# MCU.net
KiCad netlist of a schematic drawn in Altium Designer
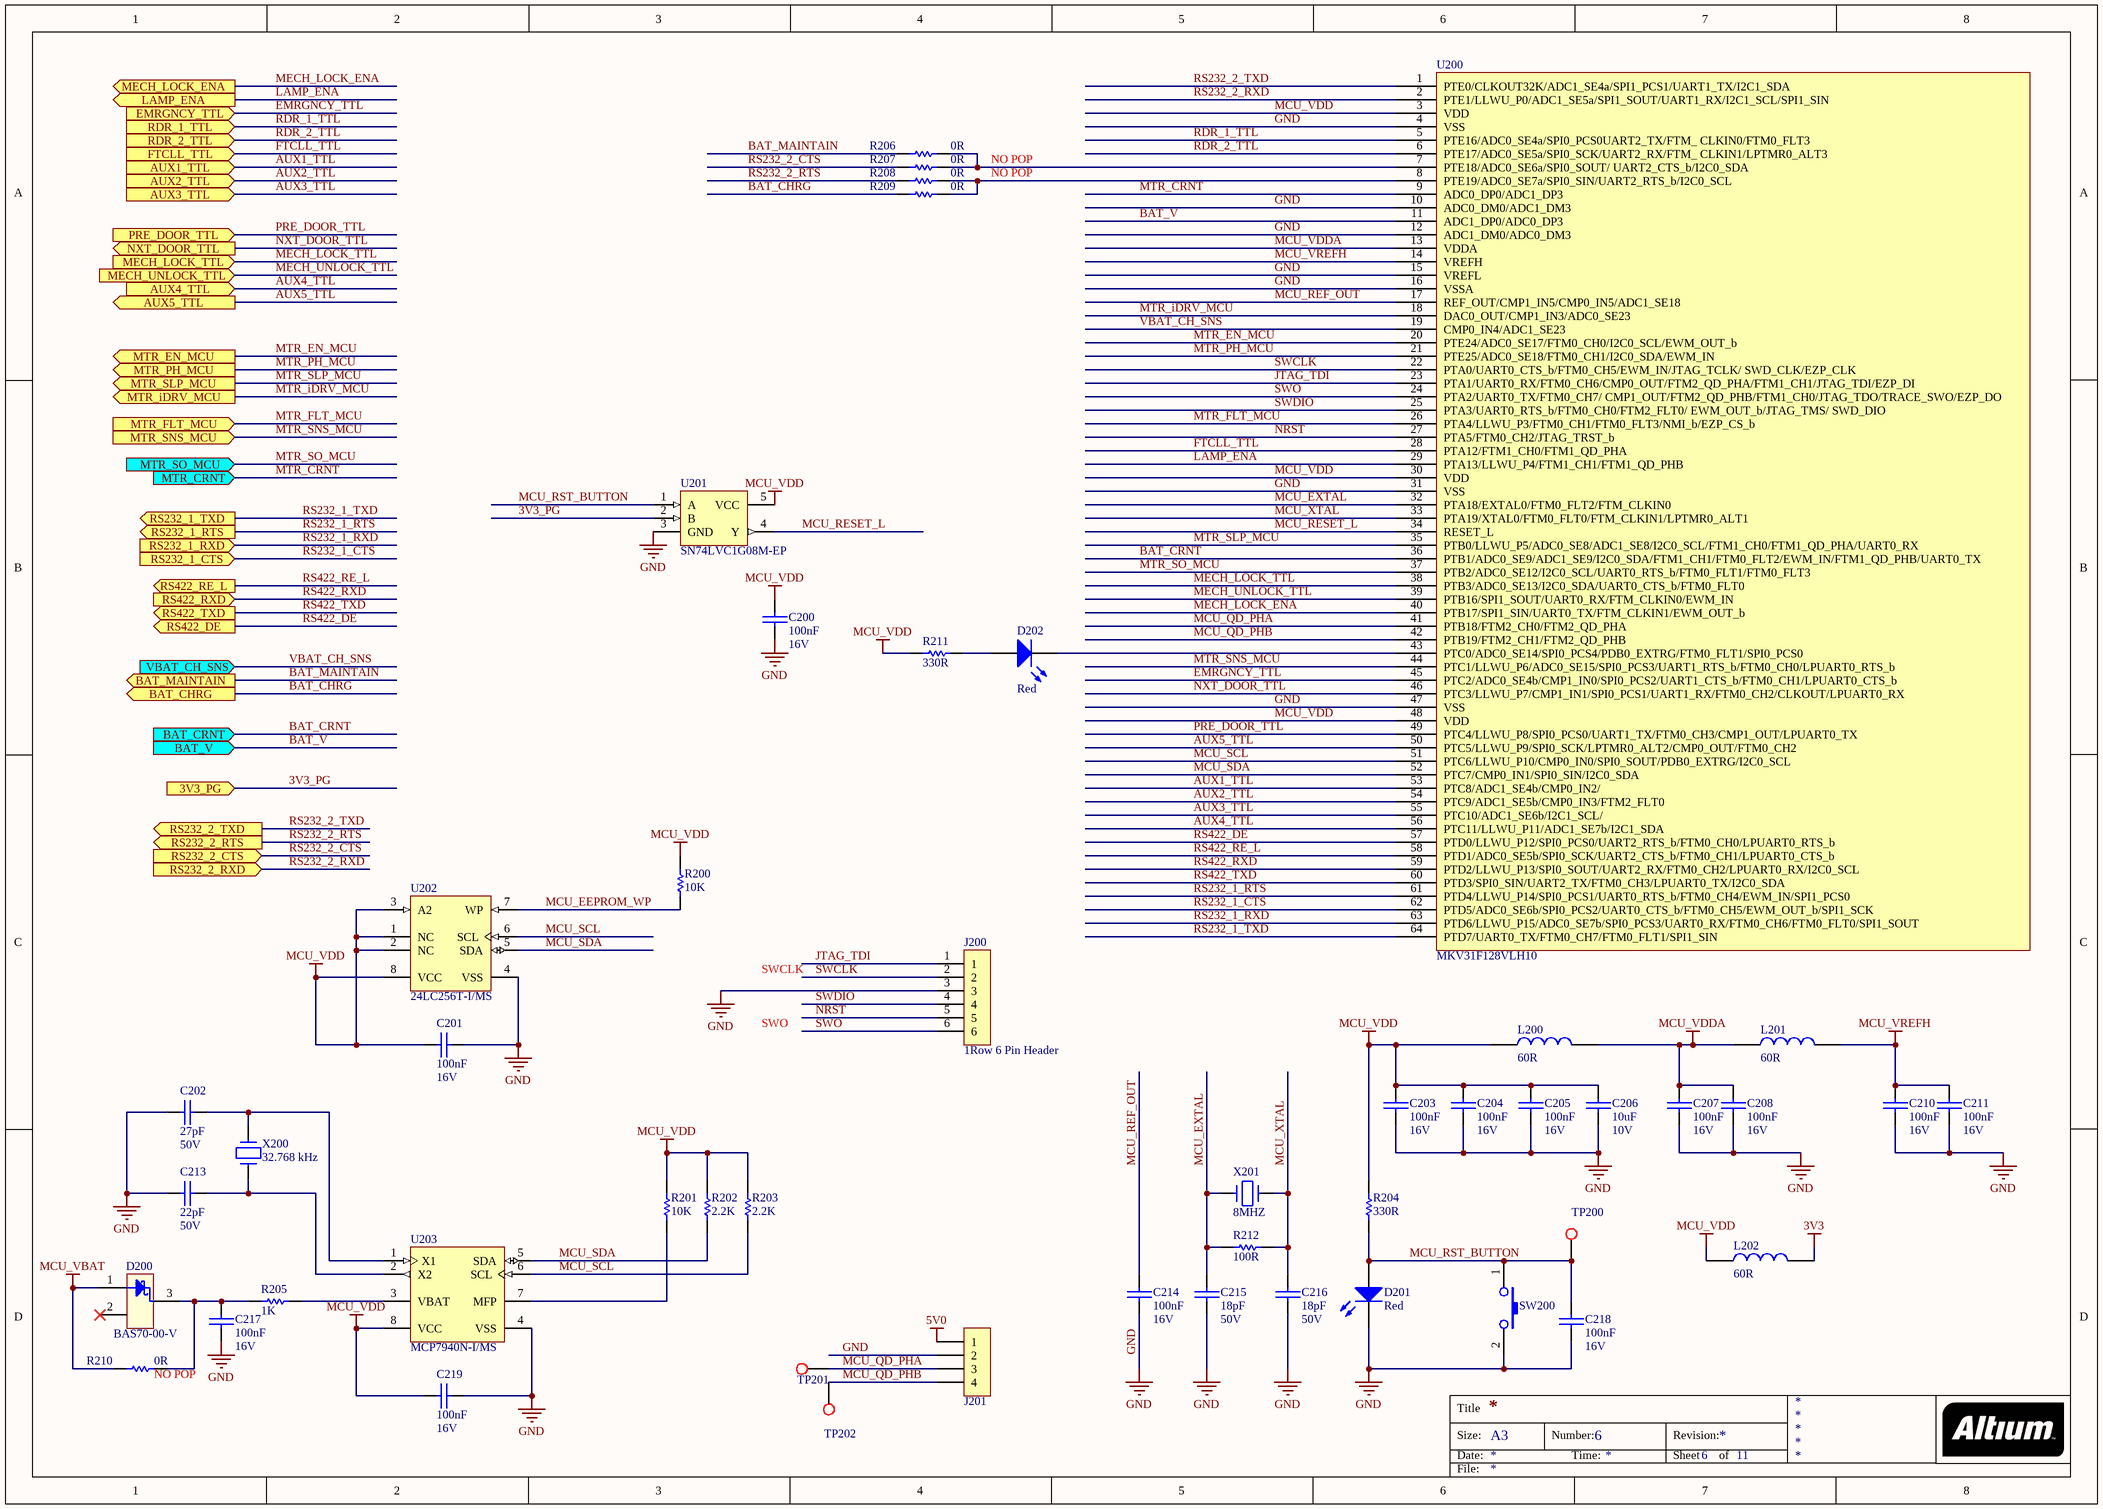
[diagram p0: MCU.SchDoc]

(export (version "E")
  (design (tool "Eeschema 10.0.6"))
  (components
    (comp (ref "C200")
      (value "100nF")
      (footprint "CAPC1005X06N")
      (description "CAP, CER, X7R, 100nF, %10, 16V, 0402")
      (fields
        (field (name "MANUFACTURER") "Murata")
        (field (name "MANUFACTURER PART NUMBER") "GRM155R71C104KA88D")
        (field (name "OPERATING VOLTAGE") "16V")
      )
      (libsource (lib "Anime_Capacitor") (part "ACC7-2100-S241-0000"))
    )
    (comp (ref "C201")
      (value "100nF")
      (footprint "CAPC1005X06N")
      (description "CAP, CER, X7R, 100nF, %10, 16V, 0402")
      (fields
        (field (name "MANUFACTURER") "Murata")
        (field (name "MANUFACTURER PART NUMBER") "GRM155R71C104KA88D")
        (field (name "OPERATING VOLTAGE") "16V")
      )
      (libsource (lib "Anime_Capacitor") (part "ACC7-2100-S241-0000"))
    )
    (comp (ref "C202")
      (value "27pF")
      (footprint "CAPC1005X06N")
      (description "CAP, CER, C0G, 27pF, %5, 50V, 0402")
      (fields
        (field (name "MANUFACTURER") "Murata")
        (field (name "MANUFACTURER PART NUMBER") "GRM1555C1H270JA01D")
        (field (name "OPERATING VOLTAGE") "50V")
      )
      (libsource (lib "Anime_Capacitor") (part "ACC0-Y270-S272-0000"))
    )
    (comp (ref "C203")
      (value "100nF")
      (footprint "CAPC1005X06N")
      (description "CAP, CER, X7R, 100nF, %10, 16V, 0402")
      (fields
        (field (name "MANUFACTURER") "Murata")
        (field (name "MANUFACTURER PART NUMBER") "GRM155R71C104KA88D")
        (field (name "OPERATING VOLTAGE") "16V")
      )
      (libsource (lib "Anime_Capacitor") (part "ACC7-2100-S241-0000"))
    )
    (comp (ref "C204")
      (value "100nF")
      (footprint "CAPC1005X06N")
      (description "CAP, CER, X7R, 100nF, %10, 16V, 0402")
      (fields
        (field (name "MANUFACTURER") "Murata")
        (field (name "MANUFACTURER PART NUMBER") "GRM155R71C104KA88D")
        (field (name "OPERATING VOLTAGE") "16V")
      )
      (libsource (lib "Anime_Capacitor") (part "ACC7-2100-S241-0000"))
    )
    (comp (ref "C205")
      (value "100nF")
      (footprint "CAPC1005X06N")
      (description "CAP, CER, X7R, 100nF, %10, 16V, 0402")
      (fields
        (field (name "MANUFACTURER") "Murata")
        (field (name "MANUFACTURER PART NUMBER") "GRM155R71C104KA88D")
        (field (name "OPERATING VOLTAGE") "16V")
      )
      (libsource (lib "Anime_Capacitor") (part "ACC7-2100-S241-0000"))
    )
    (comp (ref "C206")
      (value "10uF")
      (footprint "CAPC2012X09N")
      (description "CAP, CER, X7R, 10uF, %10, 10V, 0805")
      (fields
        (field (name "MANUFACTURER") "Murata")
        (field (name "MANUFACTURER PART NUMBER") "GRM21BR71A106KE51L")
        (field (name "OPERATING VOLTAGE") "10V")
      )
      (libsource (lib "Anime_Capacitor") (part "ACC7-4100-S431-0000"))
    )
    (comp (ref "C207")
      (value "100nF")
      (footprint "CAPC1005X06N")
      (description "CAP, CER, X7R, 100nF, %10, 16V, 0402")
      (fields
        (field (name "MANUFACTURER") "Murata")
        (field (name "MANUFACTURER PART NUMBER") "GRM155R71C104KA88D")
        (field (name "OPERATING VOLTAGE") "16V")
      )
      (libsource (lib "Anime_Capacitor") (part "ACC7-2100-S241-0000"))
    )
    (comp (ref "C208")
      (value "100nF")
      (footprint "CAPC1005X06N")
      (description "CAP, CER, X7R, 100nF, %10, 16V, 0402")
      (fields
        (field (name "MANUFACTURER") "Murata")
        (field (name "MANUFACTURER PART NUMBER") "GRM155R71C104KA88D")
        (field (name "OPERATING VOLTAGE") "16V")
      )
      (libsource (lib "Anime_Capacitor") (part "ACC7-2100-S241-0000"))
    )
    (comp (ref "C210")
      (value "100nF")
      (footprint "CAPC1005X06N")
      (description "CAP, CER, X7R, 100nF, %10, 16V, 0402")
      (fields
        (field (name "MANUFACTURER") "Murata")
        (field (name "MANUFACTURER PART NUMBER") "GRM155R71C104KA88D")
        (field (name "OPERATING VOLTAGE") "16V")
      )
      (libsource (lib "Anime_Capacitor") (part "ACC7-2100-S241-0000"))
    )
    (comp (ref "C211")
      (value "100nF")
      (footprint "CAPC1005X06N")
      (description "CAP, CER, X7R, 100nF, %10, 16V, 0402")
      (fields
        (field (name "MANUFACTURER") "Murata")
        (field (name "MANUFACTURER PART NUMBER") "GRM155R71C104KA88D")
        (field (name "OPERATING VOLTAGE") "16V")
      )
      (libsource (lib "Anime_Capacitor") (part "ACC7-2100-S241-0000"))
    )
    (comp (ref "C213")
      (value "22pF")
      (footprint "CAPC1005X06N")
      (description "CAP, CER, C0G, 22pF, %5, 50V, 0402")
      (fields
        (field (name "MANUFACTURER") "Murata")
        (field (name "MANUFACTURER PART NUMBER") "GRM1555C1H220JA01D")
        (field (name "OPERATING VOLTAGE") "50V")
      )
      (libsource (lib "Anime_Capacitor") (part "ACC0-Y220-S272-0000"))
    )
    (comp (ref "C214")
      (value "100nF")
      (footprint "CAPC1005X06N")
      (description "CAP, CER, X7R, 100nF, %10, 16V, 0402")
      (fields
        (field (name "MANUFACTURER") "Murata")
        (field (name "MANUFACTURER PART NUMBER") "GRM155R71C104KA88D")
        (field (name "OPERATING VOLTAGE") "16V")
      )
      (libsource (lib "Anime_Capacitor") (part "ACC7-2100-S241-0000"))
    )
    (comp (ref "C215")
      (value "18pF")
      (footprint "CAPC1005X06N")
      (description "CAP, CER, C0G, 18pF, %5, 50V, 0402")
      (fields
        (field (name "MANUFACTURER") "Murata")
        (field (name "MANUFACTURER PART NUMBER") "GRM1555C1H180JA01D")
        (field (name "OPERATING VOLTAGE") "50V")
      )
      (libsource (lib "Anime_Capacitor") (part "ACC0-Y180-S272-0000"))
    )
    (comp (ref "C216")
      (value "18pF")
      (footprint "CAPC1005X06N")
      (description "CAP, CER, C0G, 18pF, %5, 50V, 0402")
      (fields
        (field (name "MANUFACTURER") "Murata")
        (field (name "MANUFACTURER PART NUMBER") "GRM1555C1H180JA01D")
        (field (name "OPERATING VOLTAGE") "50V")
      )
      (libsource (lib "Anime_Capacitor") (part "ACC0-Y180-S272-0000"))
    )
    (comp (ref "C217")
      (value "100nF")
      (footprint "CAPC1005X06N")
      (description "CAP, CER, X7R, 100nF, %10, 16V, 0402")
      (fields
        (field (name "MANUFACTURER") "Murata")
        (field (name "MANUFACTURER PART NUMBER") "GRM155R71C104KA88D")
        (field (name "OPERATING VOLTAGE") "16V")
      )
      (libsource (lib "Anime_Capacitor") (part "ACC7-2100-S241-0000"))
    )
    (comp (ref "C218")
      (value "100nF")
      (footprint "CAPC1005X06N")
      (description "CAP, CER, X7R, 100nF, %10, 16V, 0402")
      (fields
        (field (name "MANUFACTURER") "Murata")
        (field (name "MANUFACTURER PART NUMBER") "GRM155R71C104KA88D")
        (field (name "OPERATING VOLTAGE") "16V")
      )
      (libsource (lib "Anime_Capacitor") (part "ACC7-2100-S241-0000"))
    )
    (comp (ref "C219")
      (value "100nF")
      (footprint "CAPC1005X06N")
      (description "CAP, CER, X7R, 100nF, %10, 16V, 0402")
      (fields
        (field (name "MANUFACTURER") "Murata")
        (field (name "MANUFACTURER PART NUMBER") "GRM155R71C104KA88D")
        (field (name "OPERATING VOLTAGE") "16V")
      )
      (libsource (lib "Anime_Capacitor") (part "ACC7-2100-S241-0000"))
    )
    (comp (ref "D200")
      (value "BAS70-00-V")
      (footprint "SOT90P247X115-3N")
      (description "Diode, Schottky, 0.41V @1mA, BAS70-00-V, SOT23")
      (fields (field (name "MANUFACTURER") "VISHAY"))
      (libsource (lib "Anime_Semiconductor") (part "AS15-820M-SI20-0002"))
    )
    (comp (ref "D201")
      (value "Red")
      (footprint "LEDSC16X08X08-2N")
      (description "LED, Red, 627 nm, 15 mcd, 120 degree, 2V, SMD, 0603")
      (fields
        (field (name "MANUFACTURER PART NUMBER") "APT1608EC")
        (field (name "MANUFACTURER") "Kingbright")
      )
      (libsource (lib "Anime_Semiconductor") (part "AS42-730L-SC50-0000"))
    )
    (comp (ref "D202")
      (value "Red")
      (footprint "LEDSC16X08X08-2N")
      (description "LED, Red, 627 nm, 15 mcd, 120 degree, 2V, SMD, 0603")
      (fields
        (field (name "MANUFACTURER PART NUMBER") "APT1608EC")
        (field (name "MANUFACTURER") "Kingbright")
      )
      (libsource (lib "Anime_Semiconductor") (part "AS42-730L-SC50-0000"))
    )
    (comp (ref "J200")
      (value "1Row 6 Pin Header")
      (footprint "AJ23-1006-T8P0-VFC0")
      (description "CON, W2B, 6 Pins, 1-Row, 2.54mm, TH, P, VER")
      (fields (field (name "MANUFACTURER") "FCI") (field (name "MANUFACTURER PART NUMBER") "68001-206HLF"))
      (libsource (lib "Anime_Connector") (part "AJ23-1006-T8P0-VFC0"))
    )
    (comp (ref "J201")
      (value "~")
      (footprint "AJ61-1004-TAPR-RNS0")
      (description "CON, Terminal, Klemens, 4 Pins, 1-Row, 5.08mm, TH, P, R")
      (fields
        (field (name "MANUFACTURER") "ON-SHORE")
        (field (name "MANUFACTURER PART NUMBER") "OSTOQ045451")
      )
      (libsource (lib "Anime_Connector") (part "AJ61-1004-TAPR-RNS0"))
    )
    (comp (ref "L200")
      (value "60R")
      (footprint "INDC2012X10N")
      (description "Inductor, Ferrite Bead, 3.5A, 60 Ohm, SMD")
      (fields
        (field (name "MANUFACTURER") "Murata")
        (field (name "MANUFACTURER PART NUMBER") "BLM21PG600SN1D")
      )
      (libsource (lib "Anime_Inductor") (part "AL5F-1600-S236-3350"))
    )
    (comp (ref "L201")
      (value "60R")
      (footprint "INDC2012X10N")
      (description "Inductor, Ferrite Bead, 3.5A, 60 Ohm, SMD")
      (fields
        (field (name "MANUFACTURER") "Murata")
        (field (name "MANUFACTURER PART NUMBER") "BLM21PG600SN1D")
      )
      (libsource (lib "Anime_Inductor") (part "AL5F-1600-S236-3350"))
    )
    (comp (ref "L202")
      (value "60R")
      (footprint "INDC2012X10N")
      (description "Inductor, Ferrite Bead, 3.5A, 60 Ohm, SMD")
      (fields
        (field (name "MANUFACTURER") "Murata")
        (field (name "MANUFACTURER PART NUMBER") "BLM21PG600SN1D")
      )
      (libsource (lib "Anime_Inductor") (part "AL5F-1600-S236-3350"))
    )
    (comp (ref "R200")
      (value "10K")
      (footprint "RESC1005X04N")
      (description "RES, E24, Thick Film, SMD, 10K, 1%, 0.1W, 0402")
      (fields
        (field (name "MANUFACTURER") "Panasonic")
        (field (name "MANUFACTURER PART NUMBER") "ERJ-2RKF1002X")
      )
      (libsource (lib "Anime_Resistor") (part "AR19-4100-S2B2-0000"))
    )
    (comp (ref "R201")
      (value "10K")
      (footprint "RESC1005X04N")
      (description "RES, E24, Thick Film, SMD, 10K, 1%, 0.1W, 0402")
      (fields
        (field (name "MANUFACTURER") "Panasonic")
        (field (name "MANUFACTURER PART NUMBER") "ERJ-2RKF1002X")
      )
      (libsource (lib "Anime_Resistor") (part "AR19-4100-S2B2-0000"))
    )
    (comp (ref "R202")
      (value "2.2K")
      (footprint "RESC1005X04N")
      (description "RES, E24, Thick Film, SMD, 2.2K, 1%, 0.1W, 0402")
      (fields
        (field (name "MANUFACTURER") "Panasonic")
        (field (name "MANUFACTURER PART NUMBER") "ERJ-2RKF2201X")
      )
      (libsource (lib "Anime_Resistor") (part "AR19-3220-S2B2-0000"))
    )
    (comp (ref "R203")
      (value "2.2K")
      (footprint "RESC1005X04N")
      (description "RES, E24, Thick Film, SMD, 2.2K, 1%, 0.1W, 0402")
      (fields
        (field (name "MANUFACTURER") "Panasonic")
        (field (name "MANUFACTURER PART NUMBER") "ERJ-2RKF2201X")
      )
      (libsource (lib "Anime_Resistor") (part "AR19-3220-S2B2-0000"))
    )
    (comp (ref "R204")
      (value "330R")
      (footprint "RESC1005X04N")
      (description "RES, E24, Thick Film, SMD, 330R, 1%, 0.1W, 0402")
      (fields
        (field (name "MANUFACTURER") "Panasonic")
        (field (name "MANUFACTURER PART NUMBER") "ERJ-2RKF3300X")
      )
      (libsource (lib "Anime_Resistor") (part "AR19-2330-S2B2-0000"))
    )
    (comp (ref "R205")
      (value "1K")
      (footprint "RESC1005X04N")
      (description "RES, E24, Thick Film, SMD, 1K, 1%, 0.1W, 0402")
      (fields
        (field (name "MANUFACTURER") "Panasonic")
        (field (name "MANUFACTURER PART NUMBER") "ERJ-2RKF1001X")
      )
      (libsource (lib "Anime_Resistor") (part "AR19-3100-S2B2-0000"))
    )
    (comp (ref "R206")
      (value "0R")
      (footprint "RESC1005X04N")
      (description "RES, Thick Film, SMD, 0R, Jumper, 0.1W, 0402")
      (fields
        (field (name "MANUFACTURER") "Panasonic")
        (field (name "MANUFACTURER PART NUMBER") "ERJ-2GE0R00X")
      )
      (libsource (lib "Anime_Resistor") (part "AR19-0000-S201-0000"))
    )
    (comp (ref "R207")
      (value "0R")
      (footprint "RESC1005X04N")
      (description "RES, Thick Film, SMD, 0R, Jumper, 0.1W, 0402")
      (fields
        (field (name "MANUFACTURER") "Panasonic")
        (field (name "MANUFACTURER PART NUMBER") "ERJ-2GE0R00X")
        (field (name "ASSEMBLY") "NO POP")
      )
      (libsource (lib "Anime_Resistor") (part "AR19-0000-S201-0000"))
    )
    (comp (ref "R208")
      (value "0R")
      (footprint "RESC1005X04N")
      (description "RES, Thick Film, SMD, 0R, Jumper, 0.1W, 0402")
      (fields
        (field (name "MANUFACTURER") "Panasonic")
        (field (name "MANUFACTURER PART NUMBER") "ERJ-2GE0R00X")
        (field (name "ASSEMBLY") "NO POP")
      )
      (libsource (lib "Anime_Resistor") (part "AR19-0000-S201-0000"))
    )
    (comp (ref "R209")
      (value "0R")
      (footprint "RESC1005X04N")
      (description "RES, Thick Film, SMD, 0R, Jumper, 0.1W, 0402")
      (fields
        (field (name "MANUFACTURER") "Panasonic")
        (field (name "MANUFACTURER PART NUMBER") "ERJ-2GE0R00X")
      )
      (libsource (lib "Anime_Resistor") (part "AR19-0000-S201-0000"))
    )
    (comp (ref "R210")
      (value "0R")
      (footprint "RESC2012X07N")
      (description "RES, Thick Film, SMD, 0R, Jumper, 0.125W, 0805")
      (fields
        (field (name "MANUFACTURER") "Panasonic")
        (field (name "MANUFACTURER PART NUMBER") "ERJ-6GEY0R00V")
        (field (name "ASSEMBLY") "NO POP")
      )
      (libsource (lib "Anime_Resistor") (part "AR19-0000-S407-0000"))
    )
    (comp (ref "R211")
      (value "330R")
      (footprint "RESC1005X04N")
      (description "RES, E24, Thick Film, SMD, 330R, 1%, 0.1W, 0402")
      (fields
        (field (name "MANUFACTURER") "Panasonic")
        (field (name "MANUFACTURER PART NUMBER") "ERJ-2RKF3300X")
      )
      (libsource (lib "Anime_Resistor") (part "AR19-2330-S2B2-0000"))
    )
    (comp (ref "R212")
      (value "100R")
      (footprint "RESC1005X04N")
      (description "RES, E24, Thick Film, SMD, 100R, 1%, 0.1W, 0402")
      (fields
        (field (name "MANUFACTURER") "Panasonic")
        (field (name "MANUFACTURER PART NUMBER") "ERJ-2RKF1000X")
      )
      (libsource (lib "Anime_Resistor") (part "AR19-2100-S2B2-0000"))
    )
    (comp (ref "SW200")
      (value "Push Button")
      (footprint "AE22-010S-0000-0000")
      (description "Switch, Push, SMD 6.6x6.0mm, Trip Force 350g")
      (fields
        (field (name "MANUFACTURER") "Panasonic")
        (field (name "MANUFACTURER PART NUMBER") "EVQ-Q2203W")
      )
      (libsource (lib "Anime_Electromechanical") (part "AE22-010S-0000-0000"))
    )
    (comp (ref "TP200")
      (value "AEMT-C00S-1000-0000")
      (footprint "TP100")
      (description "Test Point, Circular, 1mm")
      (libsource (lib "Anime_Electromechanical") (part "AEMT-C00S-1000-0000"))
    )
    (comp (ref "TP201")
      (value "AEMT-C00S-1000-0000")
      (footprint "TP100")
      (description "Test Point, Circular, 1mm")
      (libsource (lib "Anime_Electromechanical") (part "AEMT-C00S-1000-0000"))
    )
    (comp (ref "TP202")
      (value "AEMT-C00S-1000-0000")
      (footprint "TP100")
      (description "Test Point, Circular, 1mm")
      (libsource (lib "Anime_Electromechanical") (part "AEMT-C00S-1000-0000"))
    )
    (comp (ref "U200")
      (value "MKV31F128VLH10")
      (footprint "TSQFP50P1200X1200X160-64N")
      (description "IC, Embedded, Microcontroller, MKV31F128VLH10, LQFP64")
      (fields (field (name "MANUFACTURER") "Freescale"))
      (libsource (lib "Anime_IC") (part "AT35-0000-SF80-1840"))
    )
    (comp (ref "U201")
      (value "SN74LVC1G08M-EP")
      (footprint "SOT65P210X110-5N")
      (description "IC, Logic, AND Gate, SN74LVC1G08M-EP, SOT353")
      (fields
        (field (name "MANUFACTURER") "Texas Instruments")
        (field (name "MANUFACTURER PART NUMBER") "SN74LVC1G08MDCKREP")
      )
      (libsource (lib "Anime_IC") (part "AT66-0000-SI20-0460"))
    )
    (comp (ref "U202")
      (value "24LC256T-I/MS")
      (footprint "MSOP-MS8_N")
      (description "256Kbit, 400kHz, 2.5V, I2C Serial EEPROM, 8-Pin MSOP, Industrial Temperature, Tape and Reel")
      (fields (field (name "MANUFACTURER") "Microchip"))
      (libsource (lib "Microchip I2C Serial EEPROM") (part "24LC256T-I/MS"))
    )
    (comp (ref "U203")
      (value "MCP7940N-I/MS")
      (footprint "MSOP-MS8_N")
      (fields (field (name "MANUFACTURER") "Microchip"))
      (libsource (lib "Microchip Interface") (part "MCP7940N-I/MS"))
    )
    (comp (ref "X200")
      (value "32.768 kHz")
      (footprint "XTAL32X15X09")
      (description "Crystal, Fund, 32.768 kHz, 10ppm, 12.5pF, SMD")
      (fields
        (field (name "MANUFACTURER") "Citizen")
        (field (name "MANUFACTURER PART NUMBER") "CM315-32.768KEZF-UT")
      )
      (libsource (lib "Anime_IC") (part "AX20-4327-S000-0000"))
    )
    (comp (ref "X201")
      (value "8MHZ")
      (footprint "XTAL50X32X13")
      (description "Crystal, Fund, 8 MHZ, 20ppm, 18pF, SMD")
      (fields
        (field (name "MANUFACTURER") "Abracon")
        (field (name "MANUFACTURER PART NUMBER") "ABM3-8.000MHZ-D2Y-T")
      )
      (libsource (lib "Anime_IC") (part "AX20-6800-S000-0000"))
    )
  )
  (nets
    (net (code "1") (name "/3V3_PG") (class "Default")
      (node (ref "U201") (pin "2") (pinfunction "B_2") (pintype "input"))
    )
    (net (code "2") (name "/AUX1_TTL") (class "Default")
      (node (ref "U200") (pin "53") (pinfunction "PTC8/ADC1_SE4b/CMP0_IN2/_53") (pintype "passive"))
    )
    (net (code "3") (name "/AUX2_TTL") (class "Default")
      (node (ref "U200") (pin "54") (pinfunction "PTC9/ADC1_SE5b/CMP0_IN3/FTM2_FLT0_54") (pintype "passive"))
    )
    (net (code "4") (name "/AUX3_TTL") (class "Default")
      (node (ref "U200") (pin "55") (pinfunction "PTC10/ADC1_SE6b/I2C1_SCL/_55") (pintype "passive"))
    )
    (net (code "5") (name "/AUX4_TTL") (class "Default")
      (node (ref "U200") (pin "56") (pinfunction "PTC11/LLWU_P11/ADC1_SE7b/I2C1_SDA_56") (pintype "passive"))
    )
    (net (code "6") (name "/AUX5_TTL") (class "Default")
      (node (ref "U200") (pin "50") (pinfunction "PTC5/LLWU_P9/SPI0_SCK/LPTMR0_ALT2/CMP0_OUT/FTM0_CH2_50") (pintype "passive"))
    )
    (net (code "7") (name "/BAT_CHRG") (class "Default")
      (node (ref "R209") (pin "1") (pinfunction "1_1") (pintype "passive"))
    )
    (net (code "8") (name "/BAT_CRNT") (class "Default")
      (node (ref "U200") (pin "36") (pinfunction "PTB1/ADC0_SE9/ADC1_SE9/I2C0_SDA/FTM1_CH1/FTM0_FLT2/EWM_IN/FTM1_QD_PHB/UART0_TX_36") (pintype "passive"))
    )
    (net (code "9") (name "/BAT_MAINTAIN") (class "Default")
      (node (ref "R206") (pin "1") (pinfunction "1_1") (pintype "passive"))
    )
    (net (code "10") (name "/BAT_V") (class "Default")
      (node (ref "U200") (pin "11") (pinfunction "ADC1_DP0/ADC0_DP3_11") (pintype "passive"))
    )
    (net (code "11") (name "/EMRGNCY_TTL") (class "Default")
      (node (ref "U200") (pin "45") (pinfunction "PTC2/ADC0_SE4b/CMP1_IN0/SPI0_PCS2/UART1_CTS_b/FTM0_CH1/LPUART0_CTS_b_45") (pintype "passive"))
    )
    (net (code "12") (name "/FTCLL_TTL") (class "Default")
      (node (ref "U200") (pin "28") (pinfunction "PTA12/FTM1_CH0/FTM1_QD_PHA_28") (pintype "passive"))
    )
    (net (code "13") (name "/JTAG_TDI") (class "Default")
      (node (ref "J200") (pin "1") (pinfunction "1_1") (pintype "passive"))
      (node (ref "U200") (pin "23") (pinfunction "PTA1/UART0_RX/FTM0_CH6/CMP0_OUT/FTM2_QD_PHA/FTM1_CH1/JTAG_TDI/EZP_DI_23") (pintype "passive"))
    )
    (net (code "14") (name "/LAMP_ENA") (class "Default")
      (node (ref "U200") (pin "29") (pinfunction "PTA13/LLWU_P4/FTM1_CH1/FTM1_QD_PHB_29") (pintype "passive"))
    )
    (net (code "15") (name "/MCU_EEPROM_WP") (class "Default")
      (node (ref "R200") (pin "1") (pinfunction "1_1") (pintype "passive"))
      (node (ref "U202") (pin "7") (pinfunction "WP_7") (pintype "input"))
    )
    (net (code "16") (name "/MCU_EXTAL") (class "Default")
      (node (ref "C215") (pin "1") (pintype "passive"))
      (node (ref "R212") (pin "1") (pinfunction "1_1") (pintype "passive"))
      (node (ref "U200") (pin "32") (pinfunction "PTA18/EXTAL0/FTM0_FLT2/FTM_CLKIN0_32") (pintype "passive"))
      (node (ref "X201") (pin "1") (pinfunction "1_1") (pintype "passive"))
    )
    (net (code "17") (name "/MCU_QD_PHA") (class "Default")
      (node (ref "J201") (pin "3") (pinfunction "3_3") (pintype "passive"))
      (node (ref "TP201") (pin "1") (pintype "passive"))
      (node (ref "U200") (pin "41") (pinfunction "PTB18/FTM2_CH0/FTM2_QD_PHA_41") (pintype "passive"))
    )
    (net (code "18") (name "/MCU_QD_PHB") (class "Default")
      (node (ref "J201") (pin "4") (pinfunction "4_4") (pintype "passive"))
      (node (ref "TP202") (pin "1") (pintype "passive"))
      (node (ref "U200") (pin "42") (pinfunction "PTB19/FTM2_CH1/FTM2_QD_PHB_42") (pintype "passive"))
    )
    (net (code "19") (name "/MCU_REF_OUT") (class "Default")
      (node (ref "C214") (pin "2") (pintype "passive"))
      (node (ref "U200") (pin "17") (pinfunction "REF_OUT/CMP1_IN5/CMP0_IN5/ADC1_SE18_17") (pintype "passive"))
    )
    (net (code "20") (name "/MCU_RESET_L") (class "Default")
      (node (ref "U200") (pin "34") (pinfunction "RESET_L_34") (pintype "passive"))
      (node (ref "U201") (pin "4") (pinfunction "Y_4") (pintype "output"))
    )
    (net (code "21") (name "/MCU_RST_BUTTON") (class "Default")
      (node (ref "C218") (pin "2") (pintype "passive"))
      (node (ref "D201") (pin "2") (pinfunction "A_2") (pintype "passive"))
      (node (ref "R204") (pin "1") (pinfunction "1_1") (pintype "passive"))
      (node (ref "SW200") (pin "1") (pinfunction "1_1") (pintype "passive"))
      (node (ref "TP200") (pin "1") (pintype "passive"))
      (node (ref "U201") (pin "1") (pinfunction "A_1") (pintype "input"))
    )
    (net (code "22") (name "/MCU_SCL") (class "Default")
      (node (ref "R203") (pin "1") (pinfunction "1_1") (pintype "passive"))
      (node (ref "U200") (pin "51") (pinfunction "PTC6/LLWU_P10/CMP0_IN0/SPI0_SOUT/PDB0_EXTRG/I2C0_SCL_51") (pintype "passive"))
      (node (ref "U202") (pin "6") (pinfunction "SCL_6") (pintype "input"))
      (node (ref "U203") (pin "6") (pinfunction "SCL_6") (pintype "input"))
    )
    (net (code "23") (name "/MCU_SDA") (class "Default")
      (node (ref "R202") (pin "1") (pinfunction "1_1") (pintype "passive"))
      (node (ref "U200") (pin "52") (pinfunction "PTC7/CMP0_IN1/SPI0_SIN/I2C0_SDA_52") (pintype "passive"))
      (node (ref "U202") (pin "5") (pinfunction "SDA_5") (pintype "bidirectional"))
      (node (ref "U203") (pin "5") (pinfunction "SDA_5") (pintype "bidirectional"))
    )
    (net (code "24") (name "/MCU_XTAL") (class "Default")
      (node (ref "C216") (pin "1") (pintype "passive"))
      (node (ref "R212") (pin "2") (pinfunction "2_2") (pintype "passive"))
      (node (ref "U200") (pin "33") (pinfunction "PTA19/XTAL0/FTM0_FLT0/FTM_CLKIN1/LPTMR0_ALT1_33") (pintype "passive"))
      (node (ref "X201") (pin "2") (pinfunction "2_2") (pintype "passive"))
    )
    (net (code "25") (name "/MECH_LOCK_ENA") (class "Default")
      (node (ref "U200") (pin "40") (pinfunction "PTB17/SPI1_SIN/UART0_TX/FTM_CLKIN1/EWM_OUT_b_40") (pintype "passive"))
    )
    (net (code "26") (name "/MECH_LOCK_TTL") (class "Default")
      (node (ref "U200") (pin "38") (pinfunction "PTB3/ADC0_SE13/I2C0_SDA/UART0_CTS_b/FTM0_FLT0_38") (pintype "passive"))
    )
    (net (code "27") (name "/MECH_UNLOCK_TTL") (class "Default")
      (node (ref "U200") (pin "39") (pinfunction "PTB16/SPI1_SOUT/UART0_RX/FTM_CLKIN0/EWM_IN_39") (pintype "passive"))
    )
    (net (code "28") (name "/MTR_CRNT") (class "Default")
      (node (ref "U200") (pin "9") (pinfunction "ADC0_DP0/ADC1_DP3_9") (pintype "passive"))
    )
    (net (code "29") (name "/MTR_EN_MCU") (class "Default")
      (node (ref "U200") (pin "20") (pinfunction "PTE24/ADC0_SE17/FTM0_CH0/I2C0_SCL/EWM_OUT_b_20") (pintype "passive"))
    )
    (net (code "30") (name "/MTR_FLT_MCU") (class "Default")
      (node (ref "U200") (pin "26") (pinfunction "PTA4/LLWU_P3/FTM0_CH1/FTM0_FLT3/NMI_b/EZP_CS_b_26") (pintype "passive"))
    )
    (net (code "31") (name "/MTR_PH_MCU") (class "Default")
      (node (ref "U200") (pin "21") (pinfunction "PTE25/ADC0_SE18/FTM0_CH1/I2C0_SDA/EWM_IN_21") (pintype "passive"))
    )
    (net (code "32") (name "/MTR_SLP_MCU") (class "Default")
      (node (ref "U200") (pin "35") (pinfunction "PTB0/LLWU_P5/ADC0_SE8/ADC1_SE8/I2C0_SCL/FTM1_CH0/FTM1_QD_PHA/UART0_RX_35") (pintype "passive"))
    )
    (net (code "33") (name "/MTR_SNS_MCU") (class "Default")
      (node (ref "U200") (pin "44") (pinfunction "PTC1/LLWU_P6/ADC0_SE15/SPI0_PCS3/UART1_RTS_b/FTM0_CH0/LPUART0_RTS_b_44") (pintype "passive"))
    )
    (net (code "34") (name "/MTR_SO_MCU") (class "Default")
      (node (ref "U200") (pin "37") (pinfunction "PTB2/ADC0_SE12/I2C0_SCL/UART0_RTS_b/FTM0_FLT1/FTM0_FLT3_37") (pintype "passive"))
    )
    (net (code "35") (name "/MTR_iDRV_MCU") (class "Default")
      (node (ref "U200") (pin "18") (pinfunction "DAC0_OUT/CMP1_IN3/ADC0_SE23_18") (pintype "passive"))
    )
    (net (code "36") (name "/NRST") (class "Default")
      (node (ref "J200") (pin "5") (pinfunction "5_5") (pintype "passive"))
      (node (ref "U200") (pin "27") (pinfunction "PTA5/FTM0_CH2/JTAG_TRST_b_27") (pintype "passive"))
    )
    (net (code "37") (name "/NXT_DOOR_TTL") (class "Default")
      (node (ref "U200") (pin "46") (pinfunction "PTC3/LLWU_P7/CMP1_IN1/SPI0_PCS1/UART1_RX/FTM0_CH2/CLKOUT/LPUART0_RX_46") (pintype "passive"))
    )
    (net (code "38") (name "/PRE_DOOR_TTL") (class "Default")
      (node (ref "U200") (pin "49") (pinfunction "PTC4/LLWU_P8/SPI0_PCS0/UART1_TX/FTM0_CH3/CMP1_OUT/LPUART0_TX_49") (pintype "passive"))
    )
    (net (code "39") (name "/RDR_1_TTL") (class "Default")
      (node (ref "U200") (pin "5") (pinfunction "PTE16/ADC0_SE4a/SPI0_PCS0UART2_TX/FTM__CLKIN0/FTM0_FLT3_5") (pintype "passive"))
    )
    (net (code "40") (name "/RDR_2_TTL") (class "Default")
      (node (ref "U200") (pin "6") (pinfunction "PTE17/ADC0_SE5a/SPI0_SCK/UART2_RX/FTM__CLKIN1/LPTMR0_ALT3_6") (pintype "passive"))
    )
    (net (code "41") (name "/RS232_1_CTS") (class "Default")
      (node (ref "U200") (pin "62") (pinfunction "PTD5/ADC0_SE6b/SPI0_PCS2/UART0_CTS_b/FTM0_CH5/EWM_OUT_b/SPI1_SCK_62") (pintype "passive"))
    )
    (net (code "42") (name "/RS232_1_RTS") (class "Default")
      (node (ref "U200") (pin "61") (pinfunction "PTD4/LLWU_P14/SPI0_PCS1/UART0_RTS_b/FTM0_CH4/EWM_IN/SPI1_PCS0_61") (pintype "passive"))
    )
    (net (code "43") (name "/RS232_1_RXD") (class "Default")
      (node (ref "U200") (pin "63") (pinfunction "PTD6/LLWU_P15/ADC0_SE7b/SPI0_PCS3/UART0_RX/FTM0_CH6/FTM0_FLT0/SPI1_SOUT_63") (pintype "passive"))
    )
    (net (code "44") (name "/RS232_1_TXD") (class "Default")
      (node (ref "U200") (pin "64") (pinfunction "PTD7/UART0_TX/FTM0_CH7/FTM0_FLT1/SPI1_SIN_64") (pintype "passive"))
    )
    (net (code "45") (name "/RS232_2_CTS") (class "Default")
      (node (ref "R207") (pin "1") (pinfunction "1_1") (pintype "passive"))
    )
    (net (code "46") (name "/RS232_2_RTS") (class "Default")
      (node (ref "R208") (pin "1") (pinfunction "1_1") (pintype "passive"))
    )
    (net (code "47") (name "/RS232_2_RXD") (class "Default")
      (node (ref "U200") (pin "2") (pinfunction "PTE1/LLWU_P0/ADC1_SE5a/SPI1_SOUT/UART1_RX/I2C1_SCL/SPI1_SIN_2") (pintype "passive"))
    )
    (net (code "48") (name "/RS232_2_TXD") (class "Default")
      (node (ref "U200") (pin "1") (pinfunction "PTE0/CLKOUT32K/ADC1_SE4a/SPI1_PCS1/UART1_TX/I2C1_SDA_1") (pintype "passive"))
    )
    (net (code "49") (name "/RS422_DE") (class "Default")
      (node (ref "U200") (pin "57") (pinfunction "PTD0/LLWU_P12/SPI0_PCS0/UART2_RTS_b/FTM0_CH0/LPUART0_RTS_b_57") (pintype "passive"))
    )
    (net (code "50") (name "/RS422_RE_L") (class "Default")
      (node (ref "U200") (pin "58") (pinfunction "PTD1/ADC0_SE5b/SPI0_SCK/UART2_CTS_b/FTM0_CH1/LPUART0_CTS_b_58") (pintype "passive"))
    )
    (net (code "51") (name "/RS422_RXD") (class "Default")
      (node (ref "U200") (pin "59") (pinfunction "PTD2/LLWU_P13/SPI0_SOUT/UART2_RX/FTM0_CH2/LPUART0_RX/I2C0_SCL_59") (pintype "passive"))
    )
    (net (code "52") (name "/RS422_TXD") (class "Default")
      (node (ref "U200") (pin "60") (pinfunction "PTD3/SPI0_SIN/UART2_TX/FTM0_CH3/LPUART0_TX/I2C0_SDA_60") (pintype "passive"))
    )
    (net (code "53") (name "/SWCLK") (class "Default")
      (node (ref "J200") (pin "2") (pinfunction "2_2") (pintype "passive"))
      (node (ref "U200") (pin "22") (pinfunction "PTA0/UART0_CTS_b/FTM0_CH5/EWM_IN/JTAG_TCLK/_SWD_CLK/EZP_CLK_22") (pintype "passive"))
    )
    (net (code "54") (name "/SWDIO") (class "Default")
      (node (ref "J200") (pin "4") (pinfunction "4_4") (pintype "passive"))
      (node (ref "U200") (pin "25") (pinfunction "PTA3/UART0_RTS_b/FTM0_CH0/FTM2_FLT0/_EWM_OUT_b/JTAG_TMS/_SWD_DIO_25") (pintype "passive"))
    )
    (net (code "55") (name "/SWO") (class "Default")
      (node (ref "J200") (pin "6") (pinfunction "6_6") (pintype "passive"))
      (node (ref "U200") (pin "24") (pinfunction "PTA2/UART0_TX/FTM0_CH7/_CMP1_OUT/FTM2_QD_PHB/FTM1_CH0/JTAG_TDO/TRACE_SWO/EZP_DO_24") (pintype "passive"))
    )
    (net (code "56") (name "/VBAT_CH_SNS") (class "Default")
      (node (ref "U200") (pin "19") (pinfunction "CMP0_IN4/ADC1_SE23_19") (pintype "passive"))
    )
    (net (code "57") (name "3V3") (class "Default")
      (node (ref "L202") (pin "2") (pinfunction "2_2") (pintype "passive"))
    )
    (net (code "58") (name "5V0") (class "Default")
      (node (ref "J201") (pin "1") (pinfunction "1_1") (pintype "passive"))
    )
    (net (code "59") (name "GND") (class "Default")
      (node (ref "C200") (pin "2") (pintype "passive"))
      (node (ref "C201") (pin "1") (pintype "passive"))
      (node (ref "C202") (pin "1") (pintype "passive"))
      (node (ref "C203") (pin "1") (pintype "passive"))
      (node (ref "C204") (pin "1") (pintype "passive"))
      (node (ref "C205") (pin "1") (pintype "passive"))
      (node (ref "C206") (pin "1") (pintype "passive"))
      (node (ref "C207") (pin "1") (pintype "passive"))
      (node (ref "C208") (pin "1") (pintype "passive"))
      (node (ref "C210") (pin "1") (pintype "passive"))
      (node (ref "C211") (pin "1") (pintype "passive"))
      (node (ref "C213") (pin "1") (pintype "passive"))
      (node (ref "C214") (pin "1") (pintype "passive"))
      (node (ref "C215") (pin "2") (pintype "passive"))
      (node (ref "C216") (pin "2") (pintype "passive"))
      (node (ref "C217") (pin "2") (pintype "passive"))
      (node (ref "C218") (pin "1") (pintype "passive"))
      (node (ref "C219") (pin "1") (pintype "passive"))
      (node (ref "D201") (pin "1") (pinfunction "K_1") (pintype "passive"))
      (node (ref "J200") (pin "3") (pinfunction "3_3") (pintype "passive"))
      (node (ref "J201") (pin "2") (pinfunction "2_2") (pintype "passive"))
      (node (ref "SW200") (pin "2") (pinfunction "2_2") (pintype "passive"))
      (node (ref "U200") (pin "10") (pinfunction "ADC0_DM0/ADC1_DM3_10") (pintype "passive"))
      (node (ref "U200") (pin "12") (pinfunction "ADC1_DM0/ADC0_DM3_12") (pintype "passive"))
      (node (ref "U200") (pin "15") (pinfunction "VREFL_15") (pintype "power_in"))
      (node (ref "U200") (pin "16") (pinfunction "VSSA_16") (pintype "power_in"))
      (node (ref "U200") (pin "31") (pinfunction "VSS_31") (pintype "power_in"))
      (node (ref "U200") (pin "4") (pinfunction "VSS_4") (pintype "power_in"))
      (node (ref "U200") (pin "47") (pinfunction "VSS_47") (pintype "power_in"))
      (node (ref "U201") (pin "3") (pinfunction "GND_3") (pintype "power_in"))
      (node (ref "U202") (pin "4") (pinfunction "VSS_4") (pintype "power_in"))
      (node (ref "U203") (pin "4") (pinfunction "VSS_4") (pintype "power_in"))
    )
    (net (code "60") (name "MCU_VBAT") (class "Default")
      (node (ref "D200") (pin "1") (pinfunction "1_1") (pintype "passive"))
      (node (ref "R210") (pin "1") (pinfunction "1_1") (pintype "passive"))
    )
    (net (code "61") (name "MCU_VDD") (class "Default")
      (node (ref "C200") (pin "1") (pintype "passive"))
      (node (ref "C201") (pin "2") (pintype "passive"))
      (node (ref "C203") (pin "2") (pintype "passive"))
      (node (ref "C204") (pin "2") (pintype "passive"))
      (node (ref "C205") (pin "2") (pintype "passive"))
      (node (ref "C206") (pin "2") (pintype "passive"))
      (node (ref "C219") (pin "2") (pintype "passive"))
      (node (ref "L200") (pin "1") (pinfunction "1_1") (pintype "passive"))
      (node (ref "L202") (pin "1") (pinfunction "1_1") (pintype "passive"))
      (node (ref "R200") (pin "2") (pinfunction "2_2") (pintype "passive"))
      (node (ref "R201") (pin "2") (pinfunction "2_2") (pintype "passive"))
      (node (ref "R202") (pin "2") (pinfunction "2_2") (pintype "passive"))
      (node (ref "R203") (pin "2") (pinfunction "2_2") (pintype "passive"))
      (node (ref "R204") (pin "2") (pinfunction "2_2") (pintype "passive"))
      (node (ref "R211") (pin "2") (pinfunction "2_2") (pintype "passive"))
      (node (ref "U200") (pin "3") (pinfunction "VDD_3") (pintype "power_in"))
      (node (ref "U200") (pin "30") (pinfunction "VDD_30") (pintype "power_in"))
      (node (ref "U200") (pin "48") (pinfunction "VDD_48") (pintype "power_in"))
      (node (ref "U201") (pin "5") (pinfunction "VCC_5") (pintype "power_in"))
      (node (ref "U202") (pin "1") (pinfunction "NC_1") (pintype "passive"))
      (node (ref "U202") (pin "2") (pinfunction "NC_2") (pintype "passive"))
      (node (ref "U202") (pin "3") (pinfunction "A2_3") (pintype "input"))
      (node (ref "U202") (pin "8") (pinfunction "VCC_8") (pintype "power_in"))
      (node (ref "U203") (pin "8") (pinfunction "VCC_8") (pintype "power_in"))
    )
    (net (code "62") (name "MCU_VDDA") (class "Default")
      (node (ref "C207") (pin "2") (pintype "passive"))
      (node (ref "C208") (pin "2") (pintype "passive"))
      (node (ref "L200") (pin "2") (pinfunction "2_2") (pintype "passive"))
      (node (ref "L201") (pin "1") (pinfunction "1_1") (pintype "passive"))
      (node (ref "U200") (pin "13") (pinfunction "VDDA_13") (pintype "power_in"))
    )
    (net (code "63") (name "MCU_VREFH") (class "Default")
      (node (ref "C210") (pin "2") (pintype "passive"))
      (node (ref "C211") (pin "2") (pintype "passive"))
      (node (ref "L201") (pin "2") (pinfunction "2_2") (pintype "passive"))
      (node (ref "U200") (pin "14") (pinfunction "VREFH_14") (pintype "power_in"))
    )
    (net (code "64") (name "Net-(C217-Pad1)") (class "Default")
      (node (ref "C217") (pin "1") (pintype "passive"))
      (node (ref "D200") (pin "3") (pinfunction "3_3") (pintype "passive"))
      (node (ref "R205") (pin "1") (pinfunction "1_1") (pintype "passive"))
      (node (ref "R210") (pin "2") (pinfunction "2_2") (pintype "passive"))
    )
    (net (code "65") (name "Net-(D202-A)") (class "Default")
      (node (ref "D202") (pin "2") (pinfunction "A_2") (pintype "passive"))
      (node (ref "R211") (pin "1") (pinfunction "1_1") (pintype "passive"))
    )
    (net (code "66") (name "Net-(D202-K)") (class "Default")
      (node (ref "D202") (pin "1") (pinfunction "K_1") (pintype "passive"))
      (node (ref "U200") (pin "43") (pinfunction "PTC0/ADC0_SE14/SPI0_PCS4/PDB0_EXTRG/FTM0_FLT1/SPI0_PCS0_43") (pintype "passive"))
    )
    (net (code "67") (name "Net-(U200-PTE18{slash}ADC0_SE6a{slash}SPI0_SOUT{slash}_UART2_CTS_b{slash}I2C0_SDA)") (class "Default")
      (node (ref "R206") (pin "2") (pinfunction "2_2") (pintype "passive"))
      (node (ref "R207") (pin "2") (pinfunction "2_2") (pintype "passive"))
      (node (ref "U200") (pin "7") (pinfunction "PTE18/ADC0_SE6a/SPI0_SOUT/_UART2_CTS_b/I2C0_SDA_7") (pintype "passive"))
    )
    (net (code "68") (name "Net-(U200-PTE19{slash}ADC0_SE7a{slash}SPI0_SIN{slash}UART2_RTS_b{slash}I2C0_SCL)") (class "Default")
      (node (ref "R208") (pin "2") (pinfunction "2_2") (pintype "passive"))
      (node (ref "R209") (pin "2") (pinfunction "2_2") (pintype "passive"))
      (node (ref "U200") (pin "8") (pinfunction "PTE19/ADC0_SE7a/SPI0_SIN/UART2_RTS_b/I2C0_SCL_8") (pintype "passive"))
    )
    (net (code "69") (name "Net-(U203-MFP)") (class "Default")
      (node (ref "R201") (pin "1") (pinfunction "1_1") (pintype "passive"))
      (node (ref "U203") (pin "7") (pinfunction "MFP_7") (pintype "open_collector"))
    )
    (net (code "70") (name "Net-(U203-VBAT)") (class "Default")
      (node (ref "R205") (pin "2") (pinfunction "2_2") (pintype "passive"))
      (node (ref "U203") (pin "3") (pinfunction "VBAT_3") (pintype "power_in"))
    )
    (net (code "71") (name "Net-(U203-X1)") (class "Default")
      (node (ref "C202") (pin "2") (pintype "passive"))
      (node (ref "U203") (pin "1") (pinfunction "X1_1") (pintype "input"))
      (node (ref "X200") (pin "2") (pinfunction "2_2") (pintype "passive"))
    )
    (net (code "72") (name "Net-(U203-X2)") (class "Default")
      (node (ref "C213") (pin "2") (pintype "passive"))
      (node (ref "U203") (pin "2") (pinfunction "X2_2") (pintype "output"))
      (node (ref "X200") (pin "1") (pinfunction "1_1") (pintype "passive"))
    )
    (net (code "73") (name "unconnected-(D200-NC-Pad2)") (class "Default")
      (node (ref "D200") (pin "2") (pinfunction "NC_2") (pintype "passive+no_connect"))
    )
  )
)
